# bateria_EPS.net
KiCad netlist of a schematic drawn in EAGLE
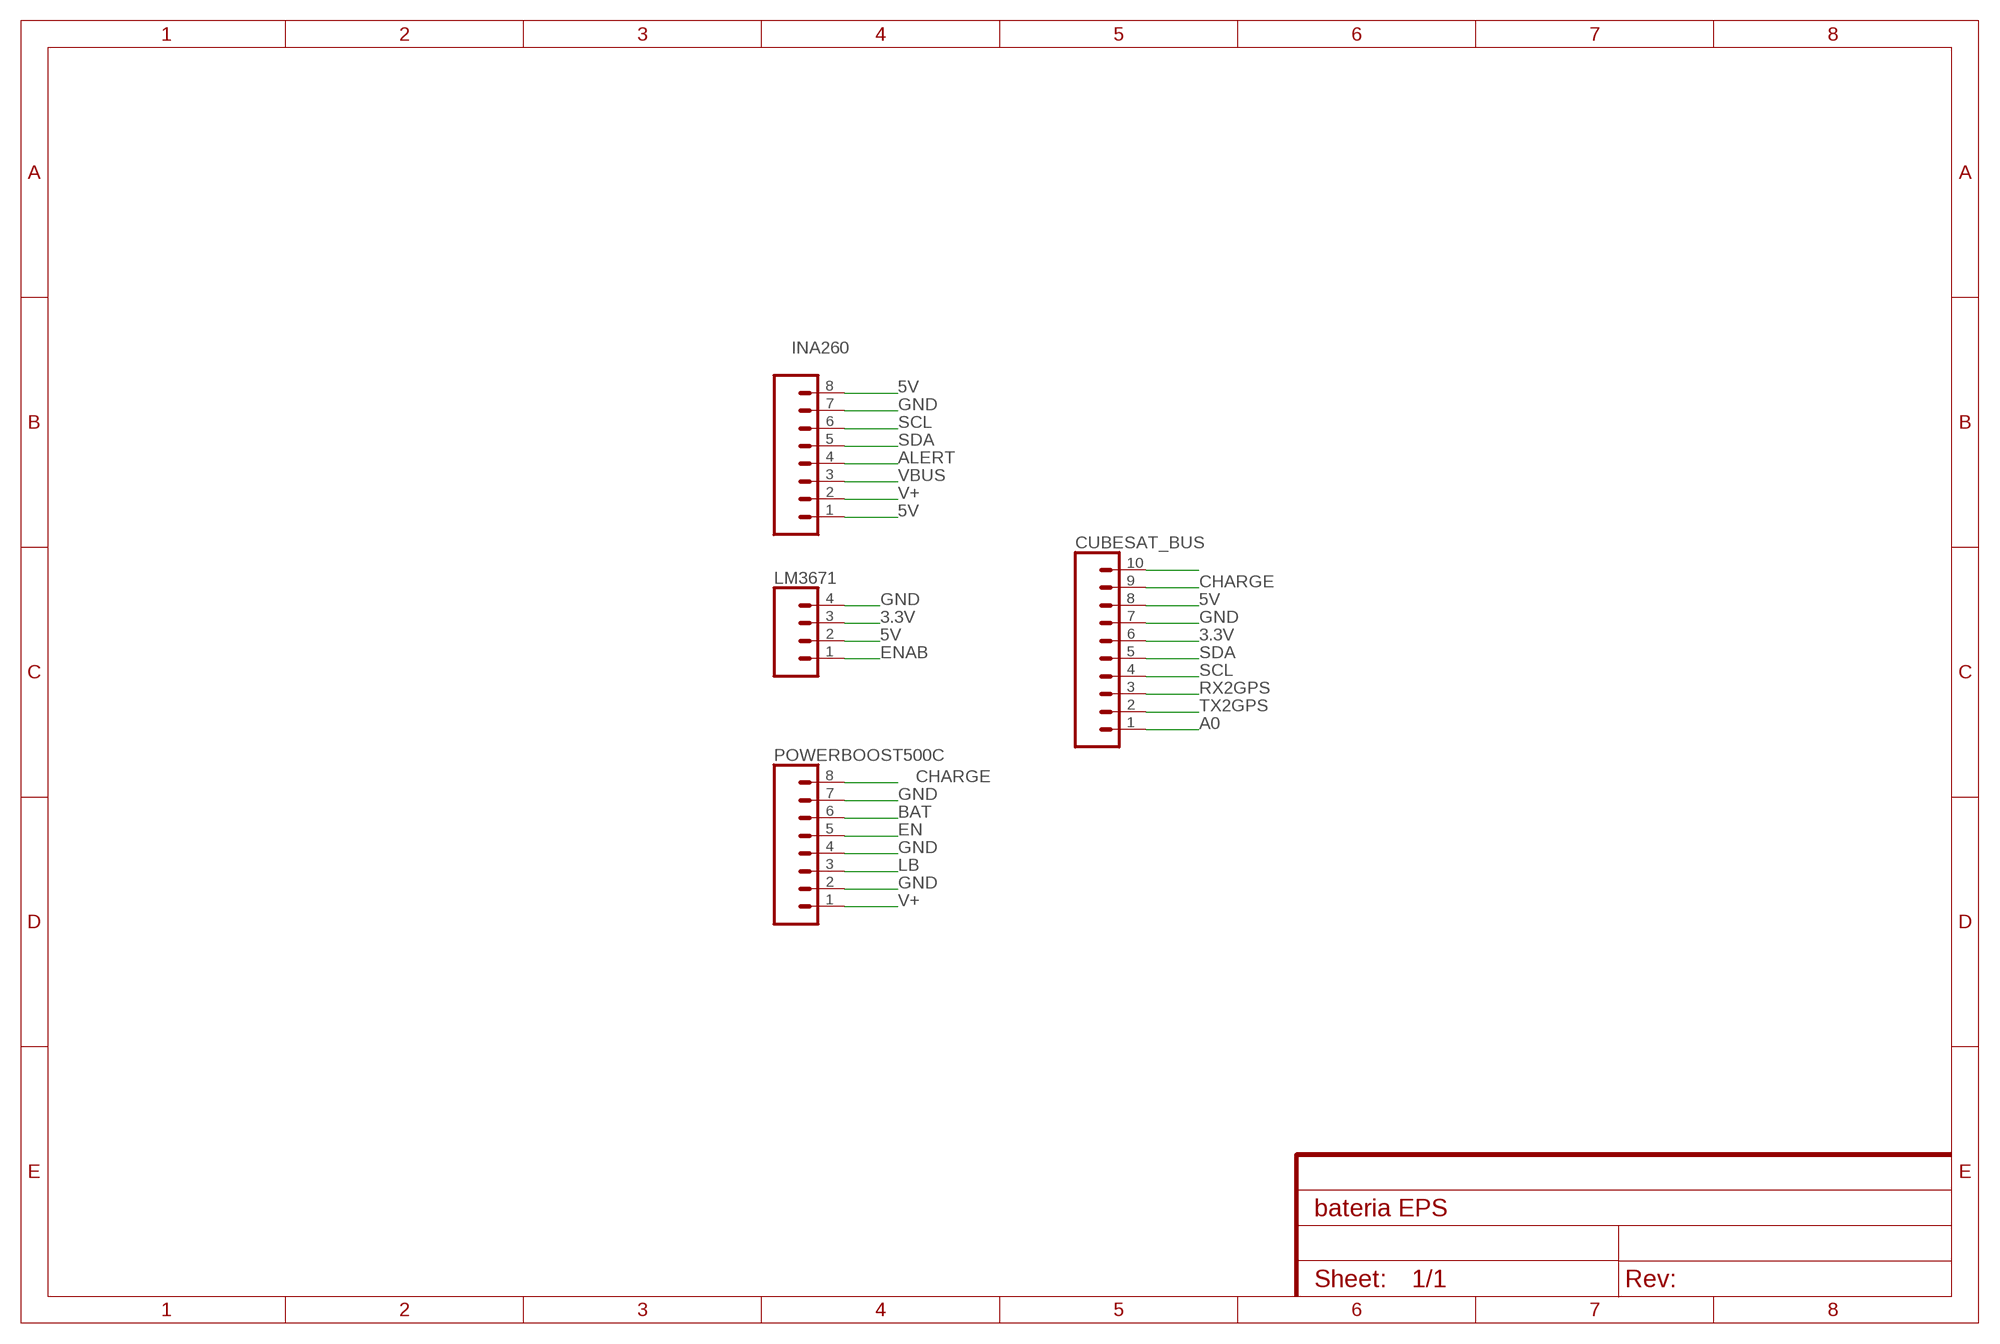
[diagram p0: schematic, sheet 1]

(export (version "E")
  (design (tool "Eeschema 10.0.6"))
  (components
    (comp (ref "CUBESAT_BUS")
      (value "CONN_10\"")
      (footprint "eagle-import:1X10")
      (libsource (lib "eagle-import") (part "CONN_10{dblquote}"))
    )
    (comp (ref "INA260")
      (value "CONN_08\"")
      (footprint "eagle-import:1X08")
      (libsource (lib "eagle-import") (part "CONN_08{dblquote}"))
    )
    (comp (ref "LM3671")
      (value "CONN_04PTH")
      (footprint "eagle-import:1X04")
      (libsource (lib "eagle-import") (part "CONN_04PTH"))
    )
    (comp (ref "POWERBOOST500C")
      (value "CONN_08\"")
      (footprint "eagle-import:1X08")
      (libsource (lib "eagle-import") (part "CONN_08{dblquote}"))
    )
  )
  (nets
    (net (code "1") (name "/3.3V") (class "Default")
      (node (ref "CUBESAT_BUS") (pin "6") (pinfunction "6_6") (pintype "passive"))
      (node (ref "LM3671") (pin "3") (pinfunction "3_3") (pintype "passive"))
    )
    (net (code "2") (name "/5V") (class "Default")
      (node (ref "CUBESAT_BUS") (pin "8") (pinfunction "8_8") (pintype "passive"))
      (node (ref "INA260") (pin "1") (pinfunction "1_1") (pintype "passive"))
      (node (ref "INA260") (pin "8") (pinfunction "8_8") (pintype "passive"))
      (node (ref "LM3671") (pin "2") (pinfunction "2_2") (pintype "passive"))
    )
    (net (code "3") (name "/A0") (class "Default")
      (node (ref "CUBESAT_BUS") (pin "1") (pinfunction "1_1") (pintype "passive"))
    )
    (net (code "4") (name "/ALERT") (class "Default")
      (node (ref "INA260") (pin "4") (pinfunction "4_4") (pintype "passive"))
    )
    (net (code "5") (name "/BAT") (class "Default")
      (node (ref "POWERBOOST500C") (pin "6") (pinfunction "6_6") (pintype "passive"))
    )
    (net (code "6") (name "/CHARGE") (class "Default")
      (node (ref "CUBESAT_BUS") (pin "9") (pinfunction "9_9") (pintype "passive"))
      (node (ref "POWERBOOST500C") (pin "8") (pinfunction "8_8") (pintype "passive"))
    )
    (net (code "7") (name "/EN") (class "Default")
      (node (ref "POWERBOOST500C") (pin "5") (pinfunction "5_5") (pintype "passive"))
    )
    (net (code "8") (name "/ENAB") (class "Default")
      (node (ref "LM3671") (pin "1") (pinfunction "1_1") (pintype "passive"))
    )
    (net (code "9") (name "/GND") (class "Default")
      (node (ref "CUBESAT_BUS") (pin "7") (pinfunction "7_7") (pintype "passive"))
      (node (ref "INA260") (pin "7") (pinfunction "7_7") (pintype "passive"))
      (node (ref "LM3671") (pin "4") (pinfunction "4_4") (pintype "passive"))
      (node (ref "POWERBOOST500C") (pin "2") (pinfunction "2_2") (pintype "passive"))
      (node (ref "POWERBOOST500C") (pin "4") (pinfunction "4_4") (pintype "passive"))
      (node (ref "POWERBOOST500C") (pin "7") (pinfunction "7_7") (pintype "passive"))
    )
    (net (code "10") (name "/LB") (class "Default")
      (node (ref "POWERBOOST500C") (pin "3") (pinfunction "3_3") (pintype "passive"))
    )
    (net (code "11") (name "/RX2GPS") (class "Default")
      (node (ref "CUBESAT_BUS") (pin "3") (pinfunction "3_3") (pintype "passive"))
    )
    (net (code "12") (name "/SCL") (class "Default")
      (node (ref "CUBESAT_BUS") (pin "4") (pinfunction "4_4") (pintype "passive"))
      (node (ref "INA260") (pin "6") (pinfunction "6_6") (pintype "passive"))
    )
    (net (code "13") (name "/SDA") (class "Default")
      (node (ref "CUBESAT_BUS") (pin "5") (pinfunction "5_5") (pintype "passive"))
      (node (ref "INA260") (pin "5") (pinfunction "5_5") (pintype "passive"))
    )
    (net (code "14") (name "/TX2GPS") (class "Default")
      (node (ref "CUBESAT_BUS") (pin "2") (pinfunction "2_2") (pintype "passive"))
    )
    (net (code "15") (name "/V+") (class "Default")
      (node (ref "INA260") (pin "2") (pinfunction "2_2") (pintype "passive"))
      (node (ref "POWERBOOST500C") (pin "1") (pinfunction "1_1") (pintype "passive"))
    )
    (net (code "16") (name "/VBUS") (class "Default")
      (node (ref "INA260") (pin "3") (pinfunction "3_3") (pintype "passive"))
    )
    (net (code "17") (name "unconnected-(CUBESAT_BUS-Pad10)") (class "Default")
      (node (ref "CUBESAT_BUS") (pin "10") (pinfunction "10_10") (pintype "passive"))
    )
  )
)
